# Candunio.net
KiCad netlist of a schematic drawn in Altium Designer
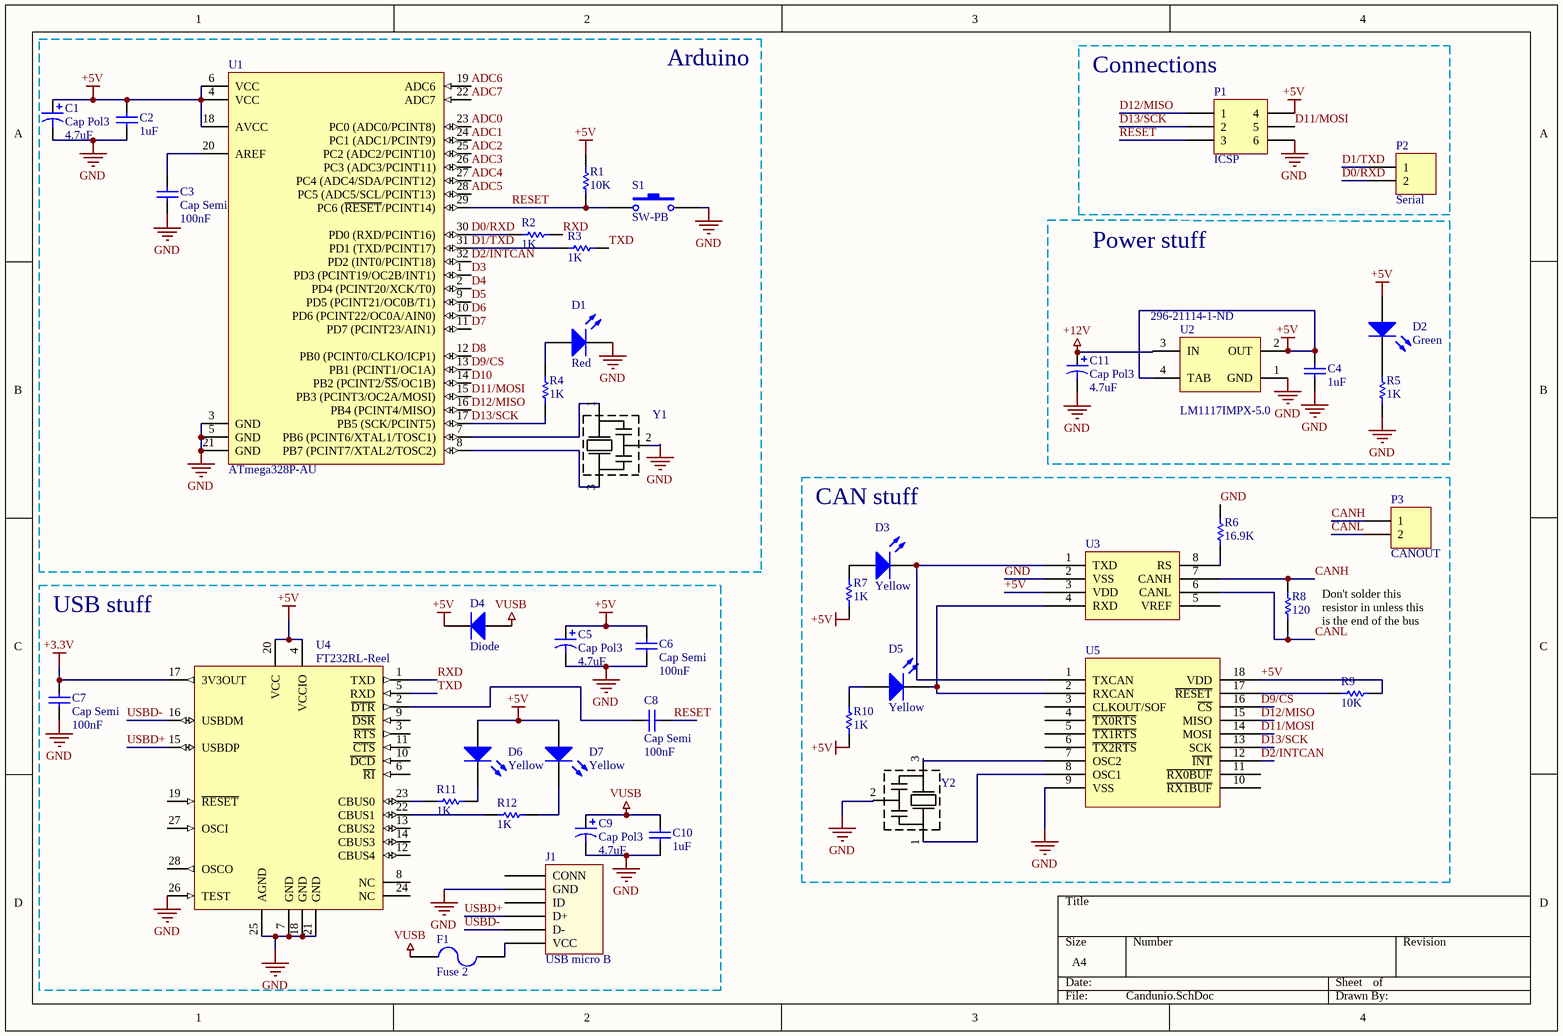
[diagram p0: Candunio.SchDoc]

(export (version "E")
  (design (tool "Eeschema 10.0.6"))
  (components
    (comp (ref "C1")
      (value "Cap Pol3")
      (footprint "CAPC3216X170N")
      (description "Polarized Capacitor (Surface Mount)")
      (fields
        (field (name "ALTIUM_VALUE") "4.7uF")
        (field (name "MANUFACTURER") "Kyocera AVX")
        (field (name "MANUFACTURER PART NUMBER") "12063C475KAT2A")
        (field (name "PUBLISHER") "Altium Limited")
      )
      (libsource (lib "Miscellaneous Devices") (part "Cap Pol3"))
    )
    (comp (ref "C2")
      (value "1uF")
      (footprint "CAPC3216X170N")
      (description "Capacitor (Semiconductor SIM Model)")
      (fields
        (field (name "MANUFACTURER") "Murata")
        (field (name "MANUFACTURER PART NUMBER") "GRM31MR71H105KA88L")
        (field (name "PUBLISHER") "Altium Limited")
      )
      (libsource (lib "Miscellaneous Devices") (part "Cap Semi"))
    )
    (comp (ref "C3")
      (value "Cap Semi")
      (footprint "CAPC3216X170N")
      (description "Capacitor (Semiconductor SIM Model)")
      (fields
        (field (name "ALTIUM_VALUE") "100nF")
        (field (name "MANUFACTURER") "Yageo")
        (field (name "MANUFACTURER PART NUMBER") "CC1206KKX7R0BB104")
        (field (name "PUBLISHER") "Altium Limited")
      )
      (libsource (lib "Miscellaneous Devices") (part "Cap Semi"))
    )
    (comp (ref "C4")
      (value "1uF")
      (footprint "CAPC3216X170N")
      (description "Capacitor (Semiconductor SIM Model)")
      (fields
        (field (name "MANUFACTURER") "Murata")
        (field (name "MANUFACTURER PART NUMBER") "GRM31MR71H105KA88L")
        (field (name "PUBLISHER") "Altium Limited")
      )
      (libsource (lib "Miscellaneous Devices") (part "Cap Semi"))
    )
    (comp (ref "C5")
      (value "Cap Pol3")
      (footprint "CAPC3216X170N")
      (description "Polarized Capacitor (Surface Mount)")
      (fields
        (field (name "ALTIUM_VALUE") "4.7uF")
        (field (name "MANUFACTURER") "Kyocera AVX")
        (field (name "MANUFACTURER PART NUMBER") "12063C475KAT2A")
        (field (name "PUBLISHER") "Altium Limited")
      )
      (libsource (lib "Miscellaneous Devices") (part "Cap Pol3"))
    )
    (comp (ref "C6")
      (value "Cap Semi")
      (footprint "CAPC3216X170N")
      (description "Capacitor (Semiconductor SIM Model)")
      (fields
        (field (name "ALTIUM_VALUE") "100nF")
        (field (name "MANUFACTURER") "Yageo")
        (field (name "MANUFACTURER PART NUMBER") "CC1206KKX7R0BB104")
        (field (name "PUBLISHER") "Altium Limited")
      )
      (libsource (lib "Miscellaneous Devices") (part "Cap Semi"))
    )
    (comp (ref "C7")
      (value "Cap Semi")
      (footprint "CAPC3216X170N")
      (description "Capacitor (Semiconductor SIM Model)")
      (fields
        (field (name "ALTIUM_VALUE") "100nF")
        (field (name "MANUFACTURER") "Yageo")
        (field (name "MANUFACTURER PART NUMBER") "CC1206KKX7R0BB104")
        (field (name "PUBLISHER") "Altium Limited")
      )
      (libsource (lib "Miscellaneous Devices") (part "Cap Semi"))
    )
    (comp (ref "C8")
      (value "Cap Semi")
      (footprint "CAPC3216X170N")
      (description "Capacitor (Semiconductor SIM Model)")
      (fields
        (field (name "ALTIUM_VALUE") "100nF")
        (field (name "MANUFACTURER") "Yageo")
        (field (name "MANUFACTURER PART NUMBER") "CC1206KKX7R0BB104")
        (field (name "PUBLISHER") "Altium Limited")
      )
      (libsource (lib "Miscellaneous Devices") (part "Cap Semi"))
    )
    (comp (ref "C9")
      (value "Cap Pol3")
      (footprint "CAPC3216X170N")
      (description "Polarized Capacitor (Surface Mount)")
      (fields
        (field (name "ALTIUM_VALUE") "4.7uF")
        (field (name "MANUFACTURER") "Kyocera AVX")
        (field (name "MANUFACTURER PART NUMBER") "12063C475KAT2A")
        (field (name "PUBLISHER") "Altium Limited")
      )
      (libsource (lib "Miscellaneous Devices") (part "Cap Pol3"))
    )
    (comp (ref "C10")
      (value "1uF")
      (footprint "CAPC3216X170N")
      (description "Capacitor (Semiconductor SIM Model)")
      (fields
        (field (name "MANUFACTURER") "Murata")
        (field (name "MANUFACTURER PART NUMBER") "GRM31MR71H105KA88L")
        (field (name "PUBLISHER") "Altium Limited")
      )
      (libsource (lib "Miscellaneous Devices") (part "Cap Semi"))
    )
    (comp (ref "C11")
      (value "Cap Pol3")
      (footprint "CAPC3216X170N")
      (description "Polarized Capacitor (Surface Mount)")
      (fields
        (field (name "ALTIUM_VALUE") "4.7uF")
        (field (name "MANUFACTURER") "Kyocera AVX")
        (field (name "MANUFACTURER PART NUMBER") "12063C475KAT2A")
        (field (name "PUBLISHER") "Altium Limited")
      )
      (libsource (lib "Miscellaneous Devices") (part "Cap Pol3"))
    )
    (comp (ref "D1")
      (value "Red")
      (footprint "LEDC3216X120NRED")
      (description "Typical RED, GREEN, YELLOW, AMBER GaAs LED")
      (fields
        (field (name "MANUFACTURER") "Broadcom Avago")
        (field (name "MANUFACTURER PART NUMBER") "HSMY-C150")
        (field (name "PUBLISHER") "Altium Limited")
      )
      (libsource (lib "Miscellaneous Devices") (part "LED2"))
    )
    (comp (ref "D2")
      (value "Green")
      (footprint "LEDC3216X120NGRN")
      (description "Typical RED, GREEN, YELLOW, AMBER GaAs LED")
      (fields
        (field (name "MANUFACTURER") "Broadcom Avago")
        (field (name "MANUFACTURER PART NUMBER") "HSMG-C150")
        (field (name "PUBLISHER") "Altium Limited")
      )
      (libsource (lib "Miscellaneous Devices") (part "LED2"))
    )
    (comp (ref "D3")
      (value "Yellow")
      (footprint "LEDC3216X120NYEL")
      (description "Typical RED, GREEN, YELLOW, AMBER GaAs LED")
      (fields
        (field (name "MANUFACTURER") "Broadcom Avago")
        (field (name "MANUFACTURER PART NUMBER") "HSMY-C150")
        (field (name "PUBLISHER") "Altium Limited")
      )
      (libsource (lib "Miscellaneous Devices") (part "LED2"))
    )
    (comp (ref "D4")
      (value "Diode")
      (footprint "DO-220AA")
      (description "Default Diode")
      (fields (field (name "PUBLISHER") "Altium Limited"))
      (libsource (lib "Miscellaneous Devices") (part "Diode"))
    )
    (comp (ref "D5")
      (value "Yellow")
      (footprint "LEDC3216X120NYEL")
      (description "Typical RED, GREEN, YELLOW, AMBER GaAs LED")
      (fields
        (field (name "MANUFACTURER") "Broadcom Avago")
        (field (name "MANUFACTURER PART NUMBER") "HSMY-C150")
        (field (name "PUBLISHER") "Altium Limited")
      )
      (libsource (lib "Miscellaneous Devices") (part "LED2"))
    )
    (comp (ref "D6")
      (value "Yellow")
      (footprint "LEDC3216X120NYEL")
      (description "Typical RED, GREEN, YELLOW, AMBER GaAs LED")
      (fields
        (field (name "MANUFACTURER") "Broadcom Avago")
        (field (name "MANUFACTURER PART NUMBER") "HSMY-C150")
        (field (name "PUBLISHER") "Altium Limited")
      )
      (libsource (lib "Miscellaneous Devices") (part "LED2"))
    )
    (comp (ref "D7")
      (value "Yellow")
      (footprint "LEDC3216X120NYEL")
      (description "Typical RED, GREEN, YELLOW, AMBER GaAs LED")
      (fields
        (field (name "MANUFACTURER") "Broadcom Avago")
        (field (name "MANUFACTURER PART NUMBER") "HSMY-C150")
        (field (name "PUBLISHER") "Altium Limited")
      )
      (libsource (lib "Miscellaneous Devices") (part "LED2"))
    )
    (comp (ref "F1")
      (value "Fuse 2")
      (footprint "FUSC4632X85N")
      (description "Fuse")
      (fields
        (field (name "PART NUMBER") "MF-MSMF050-2")
        (field (name "MANUFACTURER") "Bourns")
        (field (name "PUBLISHER") "Altium Limited")
      )
      (libsource (lib "Miscellaneous Devices") (part "Fuse 2"))
    )
    (comp (ref "J1")
      (value "USB micro B")
      (footprint "1050170001")
      (description "CONN SM TH USB MICRO MODIFIED FOR DRILL")
      (fields (field (name "PART NUMBER") "WM1399CT-ND"))
      (libsource (lib "electronpowered") (part "1050170001"))
    )
    (comp (ref "P1")
      (value "ICSP")
      (footprint "Pin Header 2x3 TH Pitch 2.54mm")
      (description "Header, 3-Pin, Dual row")
      (fields (field (name "PUBLISHER") "Altium Limited"))
      (libsource (lib "Miscellaneous Connectors") (part "Header 3X2A"))
    )
    (comp (ref "P2")
      (value "Serial")
      (footprint "Candunio v2018_7_16:Pin Header 1x2 TH Pitch 2.54mm")
      (description "Header, 2-Pin")
      (fields (field (name "PUBLISHER") "Altium Limited"))
      (libsource (lib "Miscellaneous Connectors") (part "Header 2"))
    )
    (comp (ref "P3")
      (value "CANOUT")
      (footprint "Candunio v2018_7_16:Pin Header 1x2 TH Pitch 2.54mm")
      (description "Header, 2-Pin")
      (fields (field (name "PUBLISHER") "Altium Limited"))
      (libsource (lib "Miscellaneous Connectors") (part "Header 2"))
    )
    (comp (ref "R1")
      (value "10K")
      (footprint "RESC3216X60N")
      (description "Resistor")
      (fields
        (field (name "MANUFACTURER") "Stackpole Electronics")
        (field (name "MANUFACTURER PART NUMBER") "RNCP1206FTD1K00")
      )
      (libsource (lib "Miscellaneous Devices") (part "Res1"))
    )
    (comp (ref "R2")
      (value "1K")
      (footprint "RESC3216X60N")
      (description "Resistor")
      (fields
        (field (name "MANUFACTURER") "Stackpole Electronics")
        (field (name "MANUFACTURER PART NUMBER") "RNCP1206FTD1K00")
      )
      (libsource (lib "Miscellaneous Devices") (part "Res1"))
    )
    (comp (ref "R3")
      (value "1K")
      (footprint "RESC3216X60N")
      (description "Resistor")
      (fields
        (field (name "MANUFACTURER") "Stackpole Electronics")
        (field (name "MANUFACTURER PART NUMBER") "RNCP1206FTD1K00")
      )
      (libsource (lib "Miscellaneous Devices") (part "Res1"))
    )
    (comp (ref "R4")
      (value "1K")
      (footprint "RESC3216X60N")
      (description "Resistor")
      (fields
        (field (name "MANUFACTURER") "Stackpole Electronics")
        (field (name "MANUFACTURER PART NUMBER") "RNCP1206FTD1K00")
      )
      (libsource (lib "Miscellaneous Devices") (part "Res1"))
    )
    (comp (ref "R5")
      (value "1K")
      (footprint "RESC3216X60N")
      (description "Resistor")
      (fields
        (field (name "MANUFACTURER") "Stackpole Electronics")
        (field (name "MANUFACTURER PART NUMBER") "RNCP1206FTD1K00")
      )
      (libsource (lib "Miscellaneous Devices") (part "Res1"))
    )
    (comp (ref "R6")
      (value "16.9K")
      (footprint "RESC3216X60N")
      (description "Resistor")
      (fields
        (field (name "MANUFACTURER") "TE Connectivity Holsworthy")
        (field (name "MANUFACTURER PART NUMBER") "CRGH1206F16K9")
      )
      (libsource (lib "Miscellaneous Devices") (part "Res1"))
    )
    (comp (ref "R7")
      (value "1K")
      (footprint "RESC3216X60N")
      (description "Resistor")
      (fields
        (field (name "MANUFACTURER") "Stackpole Electronics")
        (field (name "MANUFACTURER PART NUMBER") "RNCP1206FTD1K00")
      )
      (libsource (lib "Miscellaneous Devices") (part "Res1"))
    )
    (comp (ref "R8")
      (value "120")
      (footprint "RESC3216X60N")
      (description "Resistor")
      (fields
        (field (name "MANUFACTURER") "Vishay")
        (field (name "MANUFACTURER PART NUMBER") "CRCW1206120RFKEAHP")
      )
      (libsource (lib "Miscellaneous Devices") (part "Res1"))
    )
    (comp (ref "R9")
      (value "10K")
      (footprint "RESC3216X60N")
      (description "Resistor")
      (fields
        (field (name "MANUFACTURER") "Stackpole Electronics")
        (field (name "MANUFACTURER PART NUMBER") "RNCP1206FTD10K0")
      )
      (libsource (lib "Miscellaneous Devices") (part "Res1"))
    )
    (comp (ref "R10")
      (value "1K")
      (footprint "RESC3216X60N")
      (description "Resistor")
      (fields
        (field (name "MANUFACTURER") "Stackpole Electronics")
        (field (name "MANUFACTURER PART NUMBER") "RNCP1206FTD1K00")
      )
      (libsource (lib "Miscellaneous Devices") (part "Res1"))
    )
    (comp (ref "R11")
      (value "1K")
      (footprint "RESC3216X60N")
      (description "Resistor")
      (fields
        (field (name "MANUFACTURER") "Stackpole Electronics")
        (field (name "MANUFACTURER PART NUMBER") "RNCP1206FTD1K00")
      )
      (libsource (lib "Miscellaneous Devices") (part "Res1"))
    )
    (comp (ref "R12")
      (value "1K")
      (footprint "RESC3216X60N")
      (description "Resistor")
      (fields
        (field (name "MANUFACTURER") "Stackpole Electronics")
        (field (name "MANUFACTURER PART NUMBER") "RNCP1206FTD1K00")
      )
      (libsource (lib "Miscellaneous Devices") (part "Res1"))
    )
    (comp (ref "S1")
      (value "SW-PB")
      (footprint "C1206")
      (description "Switch")
      (fields
        (field (name "MANUFACTURER") "ITT C&K")
        (field (name "MANUFACTURER PART NUMBER") "KXT331LHS")
        (field (name "PUBLISHER") "Altium Limited")
      )
      (libsource (lib "Miscellaneous Devices") (part "SW-PB"))
    )
    (comp (ref "U1")
      (value "ATmega328P-AU")
      (footprint "QFP80P900X900X120-32N")
      (fields (field (name "PUBLISHER") "Altium Limited"))
      (libsource (lib "Atmel Microcontroller 8-Bit megaAVR") (part "ATmega328P-AU"))
    )
    (comp (ref "U2")
      (value "LM1117IMPX-5.0")
      (footprint "SOT230P700X180-4N")
      (description "800mA Low-Dropout Linear Regulator, 4-pin SOT-223")
      (fields
        (field (name "PARTNUMBER") "LM1117IMPX-5.0/NOPBCT-ND")
        (field (name "MANUFACTURER") "National Semiconductor")
        (field (name "SUPPLIER PART NUMBER") "296-21114-1-ND")
        (field (name "PUBLISHER") "Altium Limited")
      )
      (libsource (lib "NSC LDO") (part "LM1117IMPX-5.0"))
    )
    (comp (ref "U3")
      (value "MCP2551-E/SN")
      (footprint "SOIC127P600X175-8N")
      (description "SOIC")
      (libsource (lib "AMSComponents") (part "MCP2551-E/SN"))
    )
    (comp (ref "U4")
      (value "FT232RL-Reel")
      (footprint "SOP65P780X200-28N")
      (description "USB UART Asynchronous Serial Data Transfer Chip, SSOP-28, Tape and Reel")
      (fields
        (field (name "MANUFACTURER") "FTDI")
        (field (name "MANUFACTURER PART NUMBER") "FT232RL-REEL")
        (field (name "PUBLISHER") "Altium Limited")
      )
      (libsource (lib "FTDI Communication UART") (part "FT232RL-Reel"))
    )
    (comp (ref "U5")
      (value "MCP2515-E/ST")
      (footprint "SOIC127P1030X265-18N")
      (description "SOIC")
      (libsource (lib "AMSComponents") (part "MCP2515-E/ST"))
    )
    (comp (ref "Y1")
      (value "CSTCE16M0V53-R0")
      (footprint "CSTCE_G")
      (fields
        (field (name "MANUFACTURER") "Murata")
        (field (name "MANUFACTURER PART NUMBER") "CSTCE16M0V53C-R0")
        (field (name "TOLERANCE") "0.5%")
      )
      (libsource (lib "AMSComponents") (part "CSTCE16M0V53-R0"))
    )
    (comp (ref "Y2")
      (value "CSTCE16M0V53-R0")
      (footprint "CSTCE_G")
      (fields
        (field (name "MANUFACTURER") "Murata")
        (field (name "MANUFACTURER PART NUMBER") "CSTCE16M0V53C-R0")
        (field (name "TOLERANCE") "0.5%")
      )
      (libsource (lib "AMSComponents") (part "CSTCE16M0V53-R0"))
    )
  )
  (nets
    (net (code "1") (name "+3.3V") (class "Default")
      (node (ref "C7") (pin "1") (pinfunction "1_1") (pintype "passive"))
      (node (ref "U4") (pin "17") (pinfunction "3V3OUT_17") (pintype "output"))
    )
    (net (code "2") (name "+5V") (class "Default")
      (node (ref "C1") (pin "1") (pinfunction "1_1") (pintype "passive"))
      (node (ref "C2") (pin "1") (pinfunction "1_1") (pintype "passive"))
      (node (ref "C4") (pin "1") (pinfunction "1_1") (pintype "passive"))
      (node (ref "C5") (pin "1") (pinfunction "1_1") (pintype "passive"))
      (node (ref "C6") (pin "1") (pinfunction "1_1") (pintype "passive"))
      (node (ref "D2") (pin "1") (pinfunction "A_1") (pintype "passive"))
      (node (ref "D4") (pin "1") (pinfunction "K_1") (pintype "passive"))
      (node (ref "D6") (pin "1") (pinfunction "A_1") (pintype "passive"))
      (node (ref "D7") (pin "1") (pinfunction "A_1") (pintype "passive"))
      (node (ref "P1") (pin "4") (pinfunction "4_4") (pintype "passive"))
      (node (ref "R1") (pin "1") (pinfunction "1_1") (pintype "passive"))
      (node (ref "R10") (pin "2") (pinfunction "2_2") (pintype "passive"))
      (node (ref "R7") (pin "1") (pinfunction "1_1") (pintype "passive"))
      (node (ref "R9") (pin "2") (pinfunction "2_2") (pintype "passive"))
      (node (ref "U1") (pin "18") (pinfunction "AVCC_18") (pintype "power_in"))
      (node (ref "U1") (pin "4") (pinfunction "VCC_4") (pintype "power_in"))
      (node (ref "U1") (pin "6") (pinfunction "VCC_6") (pintype "power_in"))
      (node (ref "U2") (pin "2") (pinfunction "OUT_2") (pintype "power_in"))
      (node (ref "U2") (pin "4") (pinfunction "TAB_4") (pintype "power_in"))
      (node (ref "U3") (pin "3") (pinfunction "VDD_3") (pintype "passive"))
      (node (ref "U4") (pin "20") (pinfunction "VCC_20") (pintype "power_in"))
      (node (ref "U4") (pin "4") (pinfunction "VCCIO_4") (pintype "power_in"))
      (node (ref "U5") (pin "18") (pinfunction "VDD_18") (pintype "passive"))
    )
    (net (code "3") (name "+12V") (class "Default")
      (node (ref "C11") (pin "1") (pinfunction "1_1") (pintype "passive"))
      (node (ref "U2") (pin "3") (pinfunction "IN_3") (pintype "power_in"))
    )
    (net (code "4") (name "/ADC0") (class "Default")
      (node (ref "U1") (pin "23") (pinfunction "PC0_(ADC0/PCINT8)_23") (pintype "bidirectional"))
    )
    (net (code "5") (name "/ADC1") (class "Default")
      (node (ref "U1") (pin "24") (pinfunction "PC1_(ADC1/PCINT9)_24") (pintype "bidirectional"))
    )
    (net (code "6") (name "/ADC2") (class "Default")
      (node (ref "U1") (pin "25") (pinfunction "PC2_(ADC2/PCINT10)_25") (pintype "bidirectional"))
    )
    (net (code "7") (name "/ADC3") (class "Default")
      (node (ref "U1") (pin "26") (pinfunction "PC3_(ADC3/PCINT11)_26") (pintype "bidirectional"))
    )
    (net (code "8") (name "/ADC4") (class "Default")
      (node (ref "U1") (pin "27") (pinfunction "PC4_(ADC4/SDA/PCINT12)_27") (pintype "bidirectional"))
    )
    (net (code "9") (name "/ADC5") (class "Default")
      (node (ref "U1") (pin "28") (pinfunction "PC5_(ADC5/SCL/PCINT13)_28") (pintype "bidirectional"))
    )
    (net (code "10") (name "/ADC6") (class "Default")
      (node (ref "U1") (pin "19") (pinfunction "ADC6_19") (pintype "input"))
    )
    (net (code "11") (name "/ADC7") (class "Default")
      (node (ref "U1") (pin "22") (pinfunction "ADC7_22") (pintype "input"))
    )
    (net (code "12") (name "/CANH") (class "Default")
      (node (ref "P3") (pin "1") (pinfunction "1_1") (pintype "passive"))
      (node (ref "R8") (pin "1") (pinfunction "1_1") (pintype "passive"))
      (node (ref "U3") (pin "7") (pinfunction "CANH_7") (pintype "passive"))
    )
    (net (code "13") (name "/CANL") (class "Default")
      (node (ref "P3") (pin "2") (pinfunction "2_2") (pintype "passive"))
      (node (ref "R8") (pin "2") (pinfunction "2_2") (pintype "passive"))
      (node (ref "U3") (pin "6") (pinfunction "CANL_6") (pintype "passive"))
    )
    (net (code "14") (name "/D0{slash}RXD") (class "Default")
      (node (ref "P2") (pin "2") (pinfunction "2_2") (pintype "passive"))
      (node (ref "R2") (pin "1") (pinfunction "1_1") (pintype "passive"))
      (node (ref "U1") (pin "30") (pinfunction "PD0_(RXD/PCINT16)_30") (pintype "bidirectional"))
    )
    (net (code "15") (name "/D1{slash}TXD") (class "Default")
      (node (ref "P2") (pin "1") (pinfunction "1_1") (pintype "passive"))
      (node (ref "R3") (pin "1") (pinfunction "1_1") (pintype "passive"))
      (node (ref "U1") (pin "31") (pinfunction "PD1_(TXD/PCINT17)_31") (pintype "bidirectional"))
    )
    (net (code "16") (name "/D2{slash}INTCAN") (class "Default")
      (node (ref "U1") (pin "32") (pinfunction "PD2_(INT0/PCINT18)_32") (pintype "bidirectional"))
      (node (ref "U5") (pin "12") (pinfunction "~{INT}_12") (pintype "passive"))
    )
    (net (code "17") (name "/D3") (class "Default")
      (node (ref "U1") (pin "1") (pinfunction "PD3_(PCINT19/OC2B/INT1)_1") (pintype "bidirectional"))
    )
    (net (code "18") (name "/D4") (class "Default")
      (node (ref "U1") (pin "2") (pinfunction "PD4_(PCINT20/XCK/T0)_2") (pintype "bidirectional"))
    )
    (net (code "19") (name "/D5") (class "Default")
      (node (ref "U1") (pin "9") (pinfunction "PD5_(PCINT21/OC0B/T1)_9") (pintype "bidirectional"))
    )
    (net (code "20") (name "/D6") (class "Default")
      (node (ref "U1") (pin "10") (pinfunction "PD6_(PCINT22/OC0A/AIN0)_10") (pintype "bidirectional"))
    )
    (net (code "21") (name "/D7") (class "Default")
      (node (ref "U1") (pin "11") (pinfunction "PD7_(PCINT23/AIN1)_11") (pintype "bidirectional"))
    )
    (net (code "22") (name "/D8") (class "Default")
      (node (ref "U1") (pin "12") (pinfunction "PB0_(PCINT0/CLKO/ICP1)_12") (pintype "bidirectional"))
    )
    (net (code "23") (name "/D9{slash}CS") (class "Default")
      (node (ref "U1") (pin "13") (pinfunction "PB1_(PCINT1/OC1A)_13") (pintype "bidirectional"))
      (node (ref "U5") (pin "16") (pinfunction "~{CS}_16") (pintype "passive"))
    )
    (net (code "24") (name "/D10") (class "Default")
      (node (ref "U1") (pin "14") (pinfunction "PB2_(PCINT2/~{SS}/OC1B)_14") (pintype "bidirectional"))
    )
    (net (code "25") (name "/D11{slash}MOSI") (class "Default")
      (node (ref "P1") (pin "5") (pinfunction "5_5") (pintype "passive"))
      (node (ref "U1") (pin "15") (pinfunction "PB3_(PCINT3/OC2A/MOSI)_15") (pintype "bidirectional"))
      (node (ref "U5") (pin "14") (pinfunction "MOSI_14") (pintype "passive"))
    )
    (net (code "26") (name "/D12{slash}MISO") (class "Default")
      (node (ref "P1") (pin "1") (pinfunction "1_1") (pintype "passive"))
      (node (ref "U1") (pin "16") (pinfunction "PB4_(PCINT4/MISO)_16") (pintype "bidirectional"))
      (node (ref "U5") (pin "15") (pinfunction "MISO_15") (pintype "passive"))
    )
    (net (code "27") (name "/D13{slash}SCK") (class "Default")
      (node (ref "P1") (pin "2") (pinfunction "2_2") (pintype "passive"))
      (node (ref "R4") (pin "2") (pinfunction "2_2") (pintype "passive"))
      (node (ref "U1") (pin "17") (pinfunction "PB5_(SCK/PCINT5)_17") (pintype "bidirectional"))
      (node (ref "U5") (pin "13") (pinfunction "SCK_13") (pintype "passive"))
    )
    (net (code "28") (name "/RESET") (class "Default")
      (node (ref "C8") (pin "1") (pinfunction "1_1") (pintype "passive"))
      (node (ref "P1") (pin "3") (pinfunction "3_3") (pintype "passive"))
      (node (ref "R1") (pin "2") (pinfunction "2_2") (pintype "passive"))
      (node (ref "S1") (pin "1") (pinfunction "1_1") (pintype "passive"))
      (node (ref "U1") (pin "29") (pinfunction "PC6_(~{RESET}/PCINT14)_29") (pintype "bidirectional"))
    )
    (net (code "29") (name "/RXD") (class "Default")
      (node (ref "R2") (pin "2") (pinfunction "2_2") (pintype "passive"))
      (node (ref "U4") (pin "1") (pinfunction "TXD_1") (pintype "output"))
    )
    (net (code "30") (name "/TXD") (class "Default")
      (node (ref "R3") (pin "2") (pinfunction "2_2") (pintype "passive"))
      (node (ref "U4") (pin "5") (pinfunction "RXD_5") (pintype "input"))
    )
    (net (code "31") (name "/USBD+") (class "Default")
      (node (ref "J1") (pin "3") (pinfunction "D+_3") (pintype "passive"))
      (node (ref "U4") (pin "15") (pinfunction "USBDP_15") (pintype "bidirectional"))
    )
    (net (code "32") (name "/USBD-") (class "Default")
      (node (ref "J1") (pin "2") (pinfunction "D-_2") (pintype "passive"))
      (node (ref "U4") (pin "16") (pinfunction "USBDM_16") (pintype "bidirectional"))
    )
    (net (code "33") (name "GND") (class "Default")
      (node (ref "C1") (pin "2") (pinfunction "2_2") (pintype "passive"))
      (node (ref "C10") (pin "2") (pinfunction "2_2") (pintype "passive"))
      (node (ref "C11") (pin "2") (pinfunction "2_2") (pintype "passive"))
      (node (ref "C2") (pin "2") (pinfunction "2_2") (pintype "passive"))
      (node (ref "C3") (pin "2") (pinfunction "2_2") (pintype "passive"))
      (node (ref "C4") (pin "2") (pinfunction "2_2") (pintype "passive"))
      (node (ref "C5") (pin "2") (pinfunction "2_2") (pintype "passive"))
      (node (ref "C6") (pin "2") (pinfunction "2_2") (pintype "passive"))
      (node (ref "C7") (pin "2") (pinfunction "2_2") (pintype "passive"))
      (node (ref "C9") (pin "2") (pinfunction "2_2") (pintype "passive"))
      (node (ref "D1") (pin "2") (pinfunction "K_2") (pintype "passive"))
      (node (ref "J1") (pin "5") (pinfunction "GND_5") (pintype "passive"))
      (node (ref "P1") (pin "6") (pinfunction "6_6") (pintype "passive"))
      (node (ref "R5") (pin "2") (pinfunction "2_2") (pintype "passive"))
      (node (ref "R6") (pin "1") (pinfunction "1_1") (pintype "passive"))
      (node (ref "S1") (pin "2") (pinfunction "2_2") (pintype "passive"))
      (node (ref "U1") (pin "21") (pinfunction "GND_21") (pintype "power_in"))
      (node (ref "U1") (pin "3") (pinfunction "GND_3") (pintype "power_in"))
      (node (ref "U1") (pin "5") (pinfunction "GND_5") (pintype "power_in"))
      (node (ref "U2") (pin "1") (pinfunction "GND_1") (pintype "power_in"))
      (node (ref "U3") (pin "2") (pinfunction "VSS_2") (pintype "passive"))
      (node (ref "U4") (pin "18") (pinfunction "GND_18") (pintype "power_in"))
      (node (ref "U4") (pin "21") (pinfunction "GND_21") (pintype "power_in"))
      (node (ref "U4") (pin "25") (pinfunction "AGND_25") (pintype "power_in"))
      (node (ref "U4") (pin "26") (pinfunction "TEST_26") (pintype "input"))
      (node (ref "U4") (pin "7") (pinfunction "GND_7") (pintype "power_in"))
      (node (ref "U5") (pin "9") (pinfunction "VSS_9") (pintype "passive"))
      (node (ref "Y1") (pin "2") (pinfunction "2_2") (pintype "passive"))
      (node (ref "Y2") (pin "2") (pinfunction "2_2") (pintype "passive"))
    )
    (net (code "34") (name "Net-(D1-A)") (class "Default")
      (node (ref "D1") (pin "1") (pinfunction "A_1") (pintype "passive"))
      (node (ref "R4") (pin "1") (pinfunction "1_1") (pintype "passive"))
    )
    (net (code "35") (name "Net-(D2-K)") (class "Default")
      (node (ref "D2") (pin "2") (pinfunction "K_2") (pintype "passive"))
      (node (ref "R5") (pin "1") (pinfunction "1_1") (pintype "passive"))
    )
    (net (code "36") (name "Net-(D3-A)") (class "Default")
      (node (ref "D3") (pin "1") (pinfunction "A_1") (pintype "passive"))
      (node (ref "R7") (pin "2") (pinfunction "2_2") (pintype "passive"))
    )
    (net (code "37") (name "Net-(D3-K)") (class "Default")
      (node (ref "D3") (pin "2") (pinfunction "K_2") (pintype "passive"))
      (node (ref "U3") (pin "1") (pinfunction "TXD_1") (pintype "passive"))
      (node (ref "U5") (pin "1") (pinfunction "TXCAN_1") (pintype "passive"))
    )
    (net (code "38") (name "Net-(D5-A)") (class "Default")
      (node (ref "D5") (pin "1") (pinfunction "A_1") (pintype "passive"))
      (node (ref "R10") (pin "1") (pinfunction "1_1") (pintype "passive"))
    )
    (net (code "39") (name "Net-(D5-K)") (class "Default")
      (node (ref "D5") (pin "2") (pinfunction "K_2") (pintype "passive"))
      (node (ref "U3") (pin "4") (pinfunction "RXD_4") (pintype "passive"))
      (node (ref "U5") (pin "2") (pinfunction "RXCAN_2") (pintype "passive"))
    )
    (net (code "40") (name "Net-(D6-K)") (class "Default")
      (node (ref "D6") (pin "2") (pinfunction "K_2") (pintype "passive"))
      (node (ref "R11") (pin "2") (pinfunction "2_2") (pintype "passive"))
    )
    (net (code "41") (name "Net-(D7-K)") (class "Default")
      (node (ref "D7") (pin "2") (pinfunction "K_2") (pintype "passive"))
      (node (ref "R12") (pin "2") (pinfunction "2_2") (pintype "passive"))
    )
    (net (code "42") (name "Net-(J1-VCC)") (class "Default")
      (node (ref "F1") (pin "2") (pinfunction "2_2") (pintype "passive"))
      (node (ref "J1") (pin "1") (pinfunction "VCC_1") (pintype "passive"))
    )
    (net (code "43") (name "Net-(U1-AREF)") (class "Default")
      (node (ref "C3") (pin "1") (pinfunction "1_1") (pintype "passive"))
      (node (ref "U1") (pin "20") (pinfunction "AREF_20") (pintype "passive"))
    )
    (net (code "44") (name "Net-(U1-PB6_(PCINT6{slash}XTAL1{slash}TOSC1))") (class "Default")
      (node (ref "U1") (pin "7") (pinfunction "PB6_(PCINT6/XTAL1/TOSC1)_7") (pintype "bidirectional"))
      (node (ref "Y1") (pin "1") (pinfunction "1_1") (pintype "passive"))
    )
    (net (code "45") (name "Net-(U1-PB7_(PCINT7{slash}XTAL2{slash}TOSC2))") (class "Default")
      (node (ref "U1") (pin "8") (pinfunction "PB7_(PCINT7/XTAL2/TOSC2)_8") (pintype "bidirectional"))
      (node (ref "Y1") (pin "3") (pinfunction "3_3") (pintype "passive"))
    )
    (net (code "46") (name "Net-(U3-RS)") (class "Default")
      (node (ref "R6") (pin "2") (pinfunction "2_2") (pintype "passive"))
      (node (ref "U3") (pin "8") (pinfunction "RS_8") (pintype "passive"))
    )
    (net (code "47") (name "Net-(U4-CBUS0)") (class "Default")
      (node (ref "R11") (pin "1") (pinfunction "1_1") (pintype "passive"))
      (node (ref "U4") (pin "23") (pinfunction "CBUS0_23") (pintype "bidirectional"))
    )
    (net (code "48") (name "Net-(U4-CBUS1)") (class "Default")
      (node (ref "R12") (pin "1") (pinfunction "1_1") (pintype "passive"))
      (node (ref "U4") (pin "22") (pinfunction "CBUS1_22") (pintype "bidirectional"))
    )
    (net (code "49") (name "Net-(U4-~{DTR})") (class "Default")
      (node (ref "C8") (pin "2") (pinfunction "2_2") (pintype "passive"))
      (node (ref "U4") (pin "2") (pinfunction "~{DTR}_2") (pintype "output"))
    )
    (net (code "50") (name "Net-(U5-OSC1)") (class "Default")
      (node (ref "U5") (pin "8") (pinfunction "OSC1_8") (pintype "passive"))
      (node (ref "Y2") (pin "1") (pinfunction "1_1") (pintype "passive"))
    )
    (net (code "51") (name "Net-(U5-OSC2)") (class "Default")
      (node (ref "U5") (pin "7") (pinfunction "OSC2_7") (pintype "passive"))
      (node (ref "Y2") (pin "3") (pinfunction "3_3") (pintype "passive"))
    )
    (net (code "52") (name "Net-(U5-~{RESET})") (class "Default")
      (node (ref "R9") (pin "1") (pinfunction "1_1") (pintype "passive"))
      (node (ref "U5") (pin "17") (pinfunction "~{RESET}_17") (pintype "passive"))
    )
    (net (code "53") (name "VUSB") (class "Default")
      (node (ref "C10") (pin "1") (pinfunction "1_1") (pintype "passive"))
      (node (ref "C9") (pin "1") (pinfunction "1_1") (pintype "passive"))
      (node (ref "D4") (pin "2") (pinfunction "A_2") (pintype "passive"))
      (node (ref "F1") (pin "1") (pinfunction "1_1") (pintype "passive"))
    )
    (net (code "54") (name "unconnected-(J1-CONN-Pad0)") (class "Default")
      (node (ref "J1") (pin "0") (pinfunction "CONN_0") (pintype "passive"))
    )
    (net (code "55") (name "unconnected-(J1-ID-Pad4)") (class "Default")
      (node (ref "J1") (pin "4") (pinfunction "ID_4") (pintype "passive"))
    )
    (net (code "56") (name "unconnected-(U3-VREF-Pad5)") (class "Default")
      (node (ref "U3") (pin "5") (pinfunction "VREF_5") (pintype "passive"))
    )
    (net (code "57") (name "unconnected-(U4-CBUS2-Pad13)") (class "Default")
      (node (ref "U4") (pin "13") (pinfunction "CBUS2_13") (pintype "bidirectional"))
    )
    (net (code "58") (name "unconnected-(U4-CBUS3-Pad14)") (class "Default")
      (node (ref "U4") (pin "14") (pinfunction "CBUS3_14") (pintype "bidirectional"))
    )
    (net (code "59") (name "unconnected-(U4-CBUS4-Pad12)") (class "Default")
      (node (ref "U4") (pin "12") (pinfunction "CBUS4_12") (pintype "bidirectional"))
    )
    (net (code "60") (name "unconnected-(U4-NC-Pad8)") (class "Default")
      (node (ref "U4") (pin "8") (pinfunction "NC_8") (pintype "passive"))
    )
    (net (code "61") (name "unconnected-(U4-NC-Pad24)") (class "Default")
      (node (ref "U4") (pin "24") (pinfunction "NC_24") (pintype "passive"))
    )
    (net (code "62") (name "unconnected-(U4-OSCI-Pad27)") (class "Default")
      (node (ref "U4") (pin "27") (pinfunction "OSCI_27") (pintype "input"))
    )
    (net (code "63") (name "unconnected-(U4-OSCO-Pad28)") (class "Default")
      (node (ref "U4") (pin "28") (pinfunction "OSCO_28") (pintype "output"))
    )
    (net (code "64") (name "unconnected-(U4-~{CTS}-Pad11)") (class "Default")
      (node (ref "U4") (pin "11") (pinfunction "~{CTS}_11") (pintype "input"))
    )
    (net (code "65") (name "unconnected-(U4-~{DCD}-Pad10)") (class "Default")
      (node (ref "U4") (pin "10") (pinfunction "~{DCD}_10") (pintype "input"))
    )
    (net (code "66") (name "unconnected-(U4-~{DSR}-Pad9)") (class "Default")
      (node (ref "U4") (pin "9") (pinfunction "~{DSR}_9") (pintype "input"))
    )
    (net (code "67") (name "unconnected-(U4-~{RESET}-Pad19)") (class "Default")
      (node (ref "U4") (pin "19") (pinfunction "~{RESET}_19") (pintype "input"))
    )
    (net (code "68") (name "unconnected-(U4-~{RI}-Pad6)") (class "Default")
      (node (ref "U4") (pin "6") (pinfunction "~{RI}_6") (pintype "input"))
    )
    (net (code "69") (name "unconnected-(U4-~{RTS}-Pad3)") (class "Default")
      (node (ref "U4") (pin "3") (pinfunction "~{RTS}_3") (pintype "output"))
    )
    (net (code "70") (name "unconnected-(U5-CLKOUT{slash}SOF-Pad3)") (class "Default")
      (node (ref "U5") (pin "3") (pinfunction "CLKOUT/SOF_3") (pintype "passive"))
    )
    (net (code "71") (name "unconnected-(U5-~{RX0BUF}-Pad11)") (class "Default")
      (node (ref "U5") (pin "11") (pinfunction "~{RX0BUF}_11") (pintype "passive"))
    )
    (net (code "72") (name "unconnected-(U5-~{RX1BUF}-Pad10)") (class "Default")
      (node (ref "U5") (pin "10") (pinfunction "~{RX1BUF}_10") (pintype "passive"))
    )
    (net (code "73") (name "unconnected-(U5-~{TX0RTS}-Pad4)") (class "Default")
      (node (ref "U5") (pin "4") (pinfunction "~{TX0RTS}_4") (pintype "passive"))
    )
    (net (code "74") (name "unconnected-(U5-~{TX1RTS}-Pad5)") (class "Default")
      (node (ref "U5") (pin "5") (pinfunction "~{TX1RTS}_5") (pintype "passive"))
    )
    (net (code "75") (name "unconnected-(U5-~{TX2RTS}-Pad6)") (class "Default")
      (node (ref "U5") (pin "6") (pinfunction "~{TX2RTS}_6") (pintype "passive"))
    )
  )
)
